# working.net
KiCad netlist of a schematic drawn in EAGLE
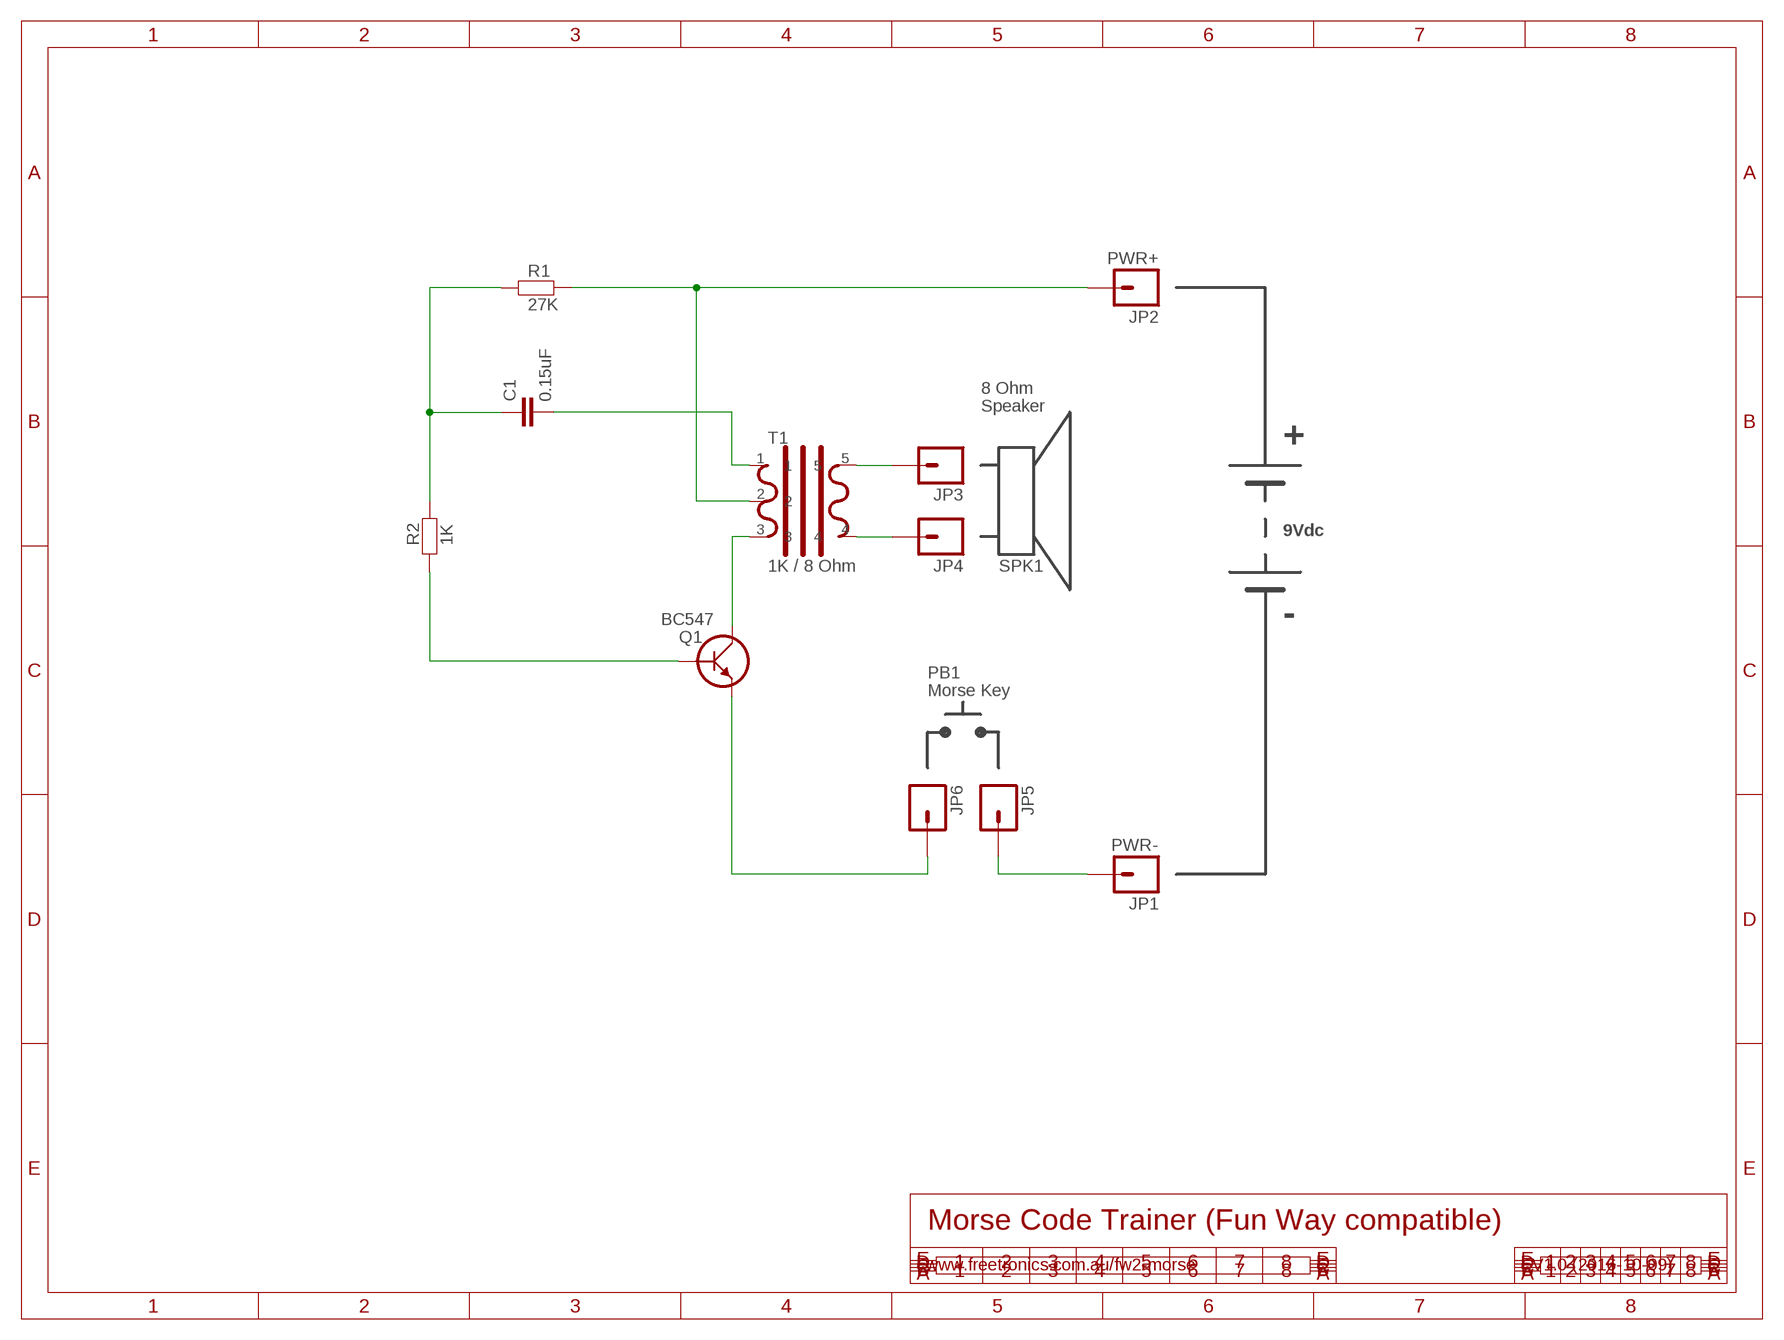
[diagram p0: schematic, sheet 1]

(export (version "E")
  (design (tool "Eeschema 10.0.6"))
  (components
    (comp (ref "C1")
      (value "0.15uF")
      (footprint "eagle-import:CAP-PTH-SMALL")
      (libsource (lib "eagle-import") (part "CAPPTH"))
    )
    (comp (ref "JP1")
      (value "PWR-")
      (footprint "eagle-import:1X01")
      (libsource (lib "eagle-import") (part "M01PTH"))
    )
    (comp (ref "JP2")
      (value "PWR+")
      (footprint "eagle-import:1X01")
      (libsource (lib "eagle-import") (part "M01PTH"))
    )
    (comp (ref "JP3")
      (value "SPKR+")
      (footprint "eagle-import:1X01")
      (libsource (lib "eagle-import") (part "M01PTH"))
    )
    (comp (ref "JP4")
      (value "SPKR-")
      (footprint "eagle-import:1X01")
      (libsource (lib "eagle-import") (part "M01PTH"))
    )
    (comp (ref "JP5")
      (value "PWR-")
      (footprint "eagle-import:1X01")
      (libsource (lib "eagle-import") (part "M01PTH"))
    )
    (comp (ref "JP6")
      (value "PWR-")
      (footprint "eagle-import:1X01")
      (libsource (lib "eagle-import") (part "M01PTH"))
    )
    (comp (ref "Q1")
      (value "BC547")
      (footprint "eagle-import:TO-92")
      (libsource (lib "eagle-import") (part "BC547"))
    )
    (comp (ref "R1")
      (value "27K")
      (footprint "eagle-import:FREETRONICS_AXIAL-0.4")
      (libsource (lib "eagle-import") (part "FREETRONICS_RESISTORPTH2"))
    )
    (comp (ref "R2")
      (value "1K")
      (footprint "eagle-import:FREETRONICS_AXIAL-0.4")
      (libsource (lib "eagle-import") (part "FREETRONICS_RESISTORPTH2"))
    )
    (comp (ref "T1")
      (value "1K / 8 Ohm")
      (footprint "eagle-import:TRANS350MW")
      (libsource (lib "eagle-import") (part "AUDIOTRANS"))
    )
  )
  (nets
    (net (code "1") (name "Net-(C1-Pad2)") (class "Default")
      (node (ref "C1") (pin "2") (pinfunction "2_2") (pintype "passive"))
      (node (ref "T1") (pin "1") (pinfunction "1_1") (pintype "bidirectional"))
    )
    (net (code "2") (name "Net-(JP1-Pad1)") (class "Default")
      (node (ref "JP1") (pin "1") (pinfunction "1_1") (pintype "passive"))
      (node (ref "JP5") (pin "1") (pinfunction "1_1") (pintype "passive"))
    )
    (net (code "3") (name "Net-(JP3-Pad1)") (class "Default")
      (node (ref "JP3") (pin "1") (pinfunction "1_1") (pintype "passive"))
      (node (ref "T1") (pin "5") (pinfunction "5_5") (pintype "bidirectional"))
    )
    (net (code "4") (name "Net-(JP4-Pad1)") (class "Default")
      (node (ref "JP4") (pin "1") (pinfunction "1_1") (pintype "passive"))
      (node (ref "T1") (pin "4") (pinfunction "4_4") (pintype "bidirectional"))
    )
    (net (code "5") (name "Net-(Q1-B)") (class "Default")
      (node (ref "Q1") (pin "2") (pinfunction "B_2") (pintype "passive"))
      (node (ref "R2") (pin "P$1") (pinfunction "1_P$1") (pintype "passive"))
    )
    (net (code "6") (name "Net-(Q1-C)") (class "Default")
      (node (ref "Q1") (pin "1") (pinfunction "C_1") (pintype "passive"))
      (node (ref "T1") (pin "3") (pinfunction "3_3") (pintype "bidirectional"))
    )
    (net (code "7") (name "Net-(Q1-E)") (class "Default")
      (node (ref "JP6") (pin "1") (pinfunction "1_1") (pintype "passive"))
      (node (ref "Q1") (pin "3") (pinfunction "E_3") (pintype "passive"))
    )
    (net (code "8") (name "Net-(R1-1)") (class "Default")
      (node (ref "C1") (pin "1") (pinfunction "1_1") (pintype "passive"))
      (node (ref "R1") (pin "P$1") (pinfunction "1_P$1") (pintype "passive"))
      (node (ref "R2") (pin "P$2") (pinfunction "2_P$2") (pintype "passive"))
    )
    (net (code "9") (name "Net-(R1-2)") (class "Default")
      (node (ref "JP2") (pin "1") (pinfunction "1_1") (pintype "passive"))
      (node (ref "R1") (pin "P$2") (pinfunction "2_P$2") (pintype "passive"))
      (node (ref "T1") (pin "2") (pinfunction "2_2") (pintype "bidirectional"))
    )
  )
)
